# antenna_bias.net
KiCad netlist of a schematic drawn in Altium Designer
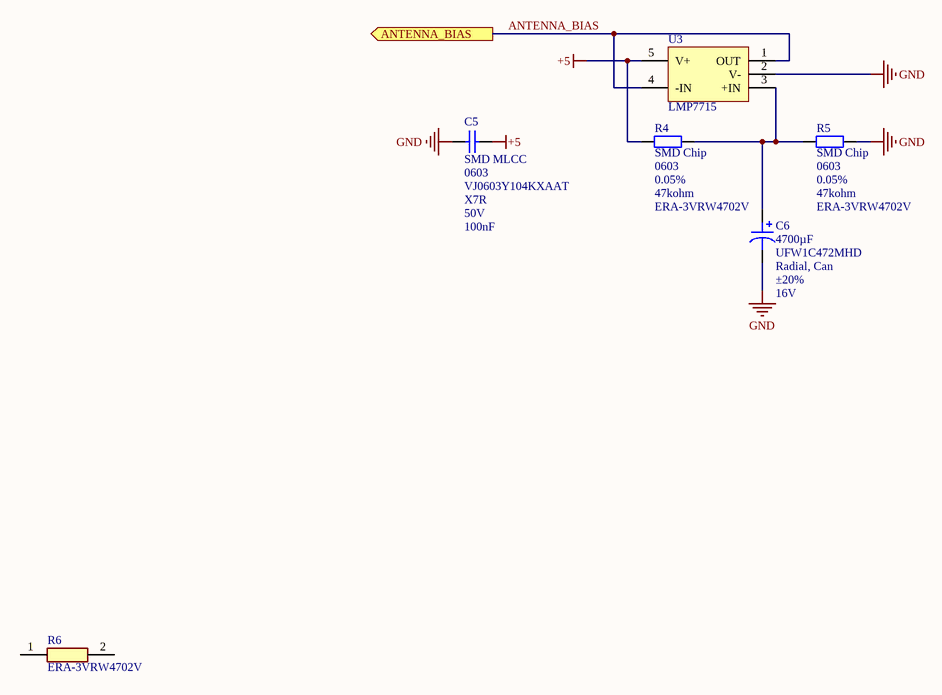
[diagram p0: antenna_bias.SchDoc]

(export (version "E")
  (design (tool "Eeschema 10.0.6"))
  (components
    (comp (ref "C5")
      (value "SMD MLCC")
      (footprint "SMD_MLCC_CAPACITOR_0603")
      (description "generic SMD MLCC capacitor")
      (fields
        (field (name "SIZE") "0603")
        (field (name "PART NUMBER") "VJ0603Y104KXAAT")
        (field (name "DIELECTRIC") "X7R")
        (field (name "VOLTAGERATING") "50V")
        (field (name "CAPACITANCE") "100nF")
      )
      (libsource (lib "altium_library") (part "SMD MLCC Capacitor"))
    )
    (comp (ref "C6")
      (value "4700µF")
      (footprint "CAP TH ALUM ELEC D16.00mm S7.50mm H25.00mm")
      (description "CAP ALUM 4700UF 20% 16V RADIAL")
      (fields
        (field (name "PART NUMBER") "UFW1C472MHD")
        (field (name "MANUFACTURER") "Nichicon")
        (field (name "PACKAGE / CASE") "Radial, Can")
        (field (name "TOLERANCE") "±20%")
        (field (name "VOLTAGE - RATED") "16V")
      )
      (libsource (lib "Celestial Altium Library - altium_library") (part "Polarised Capacitor"))
    )
    (comp (ref "R4")
      (value "SMD Chip")
      (footprint "SMD_CHIP_RESISTOR_0603")
      (description "generic SMD chip resistor")
      (fields
        (field (name "SIZE") "0603")
        (field (name "TOLERANCE") "0.05%")
        (field (name "RESISTANCE") "47kohm")
        (field (name "PART NUMBER") "ERA-3VRW4702V")
      )
      (libsource (lib "altium_library") (part "SMD Chip Resistor"))
    )
    (comp (ref "R5")
      (value "SMD Chip")
      (footprint "SMD_CHIP_RESISTOR_0603")
      (description "generic SMD chip resistor")
      (fields
        (field (name "SIZE") "0603")
        (field (name "TOLERANCE") "0.05%")
        (field (name "RESISTANCE") "47kohm")
        (field (name "PART NUMBER") "ERA-3VRW4702V")
      )
      (libsource (lib "altium_library") (part "SMD Chip Resistor"))
    )
    (comp (ref "R6")
      (value "ERA-3VRW4702V")
      (footprint "SamacSys:ERA3KV_(0603)")
      (description "Resistor")
      (libsource (lib "*") (part "ERA-3VRW4702V"))
    )
    (comp (ref "U3")
      (value "LMP7715")
      (footprint "LMP7715")
      (description "Precision, 17 MHz, Low Noise, CMOS Input Amplifier")
      (libsource (lib "altium_library") (part "LMP7715"))
    )
  )
  (nets
    (net (code "1") (name "+5") (class "Default")
      (node (ref "C5") (pin "1") (pinfunction "1_1") (pintype "passive"))
      (node (ref "R4") (pin "1") (pinfunction "1_1") (pintype "passive"))
      (node (ref "U3") (pin "5") (pinfunction "V+_5") (pintype "passive"))
    )
    (net (code "2") (name "/ANTENNA_BIAS") (class "Default")
      (node (ref "U3") (pin "1") (pinfunction "OUT_1") (pintype "passive"))
      (node (ref "U3") (pin "4") (pinfunction "-IN_4") (pintype "passive"))
    )
    (net (code "3") (name "GND") (class "Default")
      (node (ref "C5") (pin "2") (pinfunction "2_2") (pintype "passive"))
      (node (ref "C6") (pin "2") (pinfunction "2_2") (pintype "passive"))
      (node (ref "R5") (pin "2") (pinfunction "2_2") (pintype "passive"))
      (node (ref "U3") (pin "2") (pinfunction "V-_2") (pintype "passive"))
    )
    (net (code "4") (name "Net-(U3-+IN)") (class "Default")
      (node (ref "C6") (pin "1") (pinfunction "1_1") (pintype "passive"))
      (node (ref "R4") (pin "2") (pinfunction "2_2") (pintype "passive"))
      (node (ref "R5") (pin "1") (pinfunction "1_1") (pintype "passive"))
      (node (ref "U3") (pin "3") (pinfunction "+IN_3") (pintype "passive"))
    )
    (net (code "5") (name "unconnected-(R6-Pad1)") (class "Default")
      (node (ref "R6") (pin "1") (pinfunction "1_1") (pintype "passive"))
    )
    (net (code "6") (name "unconnected-(R6-Pad2)") (class "Default")
      (node (ref "R6") (pin "2") (pinfunction "2_2") (pintype "passive"))
    )
  )
)
